# ov7670.net
KiCad netlist of a schematic drawn in EAGLE
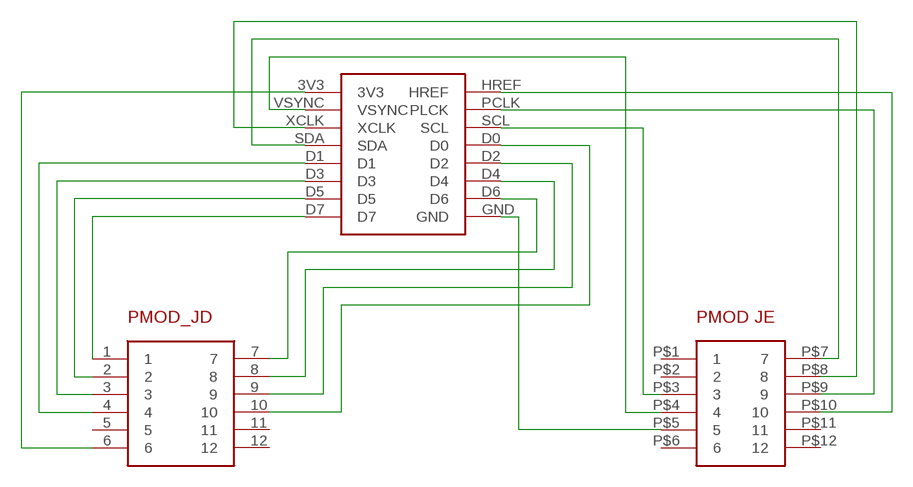
[diagram p0: schematic, sheet 1]

(export (version "E")
  (design (tool "Eeschema 10.0.6"))
  (components
    (comp (ref "D6")
      (value "OV7670")
      (footprint "eagle-import:OV7670")
      (libsource (lib "eagle-import") (part "OV7670"))
    )
    (comp (ref "U$2")
      (value "PMOD_JD")
      (footprint "eagle-import:PMOD_JD")
      (libsource (lib "eagle-import") (part "PMOD_JD"))
    )
    (comp (ref "U$3")
      (value "PMOD_JE")
      (footprint "eagle-import:PMOD_JE")
      (libsource (lib "eagle-import") (part "PMOD_JE"))
    )
  )
  (nets
    (net (code "1") (name "Net-(D6-PLCK)") (class "Default")
      (node (ref "D6") (pin "PCLK") (pinfunction "PLCK_PCLK") (pintype "bidirectional"))
      (node (ref "U$3") (pin "P$9") (pinfunction "9_P$9") (pintype "bidirectional"))
    )
    (net (code "2") (name "Net-(D6-Pad3V3)") (class "Default")
      (node (ref "D6") (pin "3V3") (pinfunction "3V3_3V3") (pintype "bidirectional"))
      (node (ref "U$2") (pin "6") (pinfunction "6_6") (pintype "bidirectional"))
    )
    (net (code "3") (name "Net-(D6-PadD0)") (class "Default")
      (node (ref "D6") (pin "D0") (pinfunction "D0_D0") (pintype "bidirectional"))
      (node (ref "U$2") (pin "10") (pinfunction "10_10") (pintype "bidirectional"))
    )
    (net (code "4") (name "Net-(D6-PadD1)") (class "Default")
      (node (ref "D6") (pin "D1") (pinfunction "D1_D1") (pintype "bidirectional"))
      (node (ref "U$2") (pin "4") (pinfunction "4_4") (pintype "bidirectional"))
    )
    (net (code "5") (name "Net-(D6-PadD2)") (class "Default")
      (node (ref "D6") (pin "D2") (pinfunction "D2_D2") (pintype "bidirectional"))
      (node (ref "U$2") (pin "9") (pinfunction "9_9") (pintype "bidirectional"))
    )
    (net (code "6") (name "Net-(D6-PadD3)") (class "Default")
      (node (ref "D6") (pin "D3") (pinfunction "D3_D3") (pintype "bidirectional"))
      (node (ref "U$2") (pin "3") (pinfunction "3_3") (pintype "bidirectional"))
    )
    (net (code "7") (name "Net-(D6-PadD4)") (class "Default")
      (node (ref "D6") (pin "D4") (pinfunction "D4_D4") (pintype "bidirectional"))
      (node (ref "U$2") (pin "8") (pinfunction "8_8") (pintype "bidirectional"))
    )
    (net (code "8") (name "Net-(D6-PadD5)") (class "Default")
      (node (ref "D6") (pin "D5") (pinfunction "D5_D5") (pintype "bidirectional"))
      (node (ref "U$2") (pin "2") (pinfunction "2_2") (pintype "bidirectional"))
    )
    (net (code "9") (name "Net-(D6-PadD6)") (class "Default")
      (node (ref "D6") (pin "D6") (pinfunction "D6_D6") (pintype "bidirectional"))
      (node (ref "U$2") (pin "7") (pinfunction "7_7") (pintype "bidirectional"))
    )
    (net (code "10") (name "Net-(D6-PadD7)") (class "Default")
      (node (ref "D6") (pin "D7") (pinfunction "D7_D7") (pintype "bidirectional"))
      (node (ref "U$2") (pin "1") (pinfunction "1_1") (pintype "bidirectional"))
    )
    (net (code "11") (name "Net-(U$3-3)") (class "Default")
      (node (ref "D6") (pin "SCL") (pinfunction "SCL_SCL") (pintype "bidirectional"))
      (node (ref "U$3") (pin "P$3") (pinfunction "3_P$3") (pintype "bidirectional"))
    )
    (net (code "12") (name "Net-(U$3-4)") (class "Default")
      (node (ref "D6") (pin "VSYNC") (pinfunction "VSYNC_VSYNC") (pintype "bidirectional"))
      (node (ref "U$3") (pin "P$4") (pinfunction "4_P$4") (pintype "bidirectional"))
    )
    (net (code "13") (name "Net-(U$3-5)") (class "Default")
      (node (ref "D6") (pin "GND") (pinfunction "GND_GND") (pintype "bidirectional"))
      (node (ref "U$3") (pin "P$5") (pinfunction "5_P$5") (pintype "bidirectional"))
    )
    (net (code "14") (name "Net-(U$3-7)") (class "Default")
      (node (ref "D6") (pin "SDA") (pinfunction "SDA_SDA") (pintype "bidirectional"))
      (node (ref "U$3") (pin "P$7") (pinfunction "7_P$7") (pintype "bidirectional"))
    )
    (net (code "15") (name "Net-(U$3-8)") (class "Default")
      (node (ref "D6") (pin "XCLK") (pinfunction "XCLK_XCLK") (pintype "bidirectional"))
      (node (ref "U$3") (pin "P$8") (pinfunction "8_P$8") (pintype "bidirectional"))
    )
    (net (code "16") (name "Net-(U$3-10)") (class "Default")
      (node (ref "D6") (pin "HREF") (pinfunction "HREF_HREF") (pintype "bidirectional"))
      (node (ref "U$3") (pin "P$10") (pinfunction "10_P$10") (pintype "bidirectional"))
    )
    (net (code "17") (name "unconnected-(U$2-Pad5)") (class "Default")
      (node (ref "U$2") (pin "5") (pinfunction "5_5") (pintype "bidirectional"))
    )
    (net (code "18") (name "unconnected-(U$2-Pad11)") (class "Default")
      (node (ref "U$2") (pin "11") (pinfunction "11_11") (pintype "bidirectional"))
    )
    (net (code "19") (name "unconnected-(U$2-Pad12)") (class "Default")
      (node (ref "U$2") (pin "12") (pinfunction "12_12") (pintype "bidirectional"))
    )
    (net (code "20") (name "unconnected-(U$3-1-PadP$1)") (class "Default")
      (node (ref "U$3") (pin "P$1") (pinfunction "1_P$1") (pintype "bidirectional"))
    )
    (net (code "21") (name "unconnected-(U$3-2-PadP$2)") (class "Default")
      (node (ref "U$3") (pin "P$2") (pinfunction "2_P$2") (pintype "bidirectional"))
    )
    (net (code "22") (name "unconnected-(U$3-6-PadP$6)") (class "Default")
      (node (ref "U$3") (pin "P$6") (pinfunction "6_P$6") (pintype "bidirectional"))
    )
    (net (code "23") (name "unconnected-(U$3-11-PadP$11)") (class "Default")
      (node (ref "U$3") (pin "P$11") (pinfunction "11_P$11") (pintype "bidirectional"))
    )
    (net (code "24") (name "unconnected-(U$3-12-PadP$12)") (class "Default")
      (node (ref "U$3") (pin "P$12") (pinfunction "12_P$12") (pintype "bidirectional"))
    )
  )
)
